# meteo_1.net
KiCad netlist of a schematic drawn in EAGLE
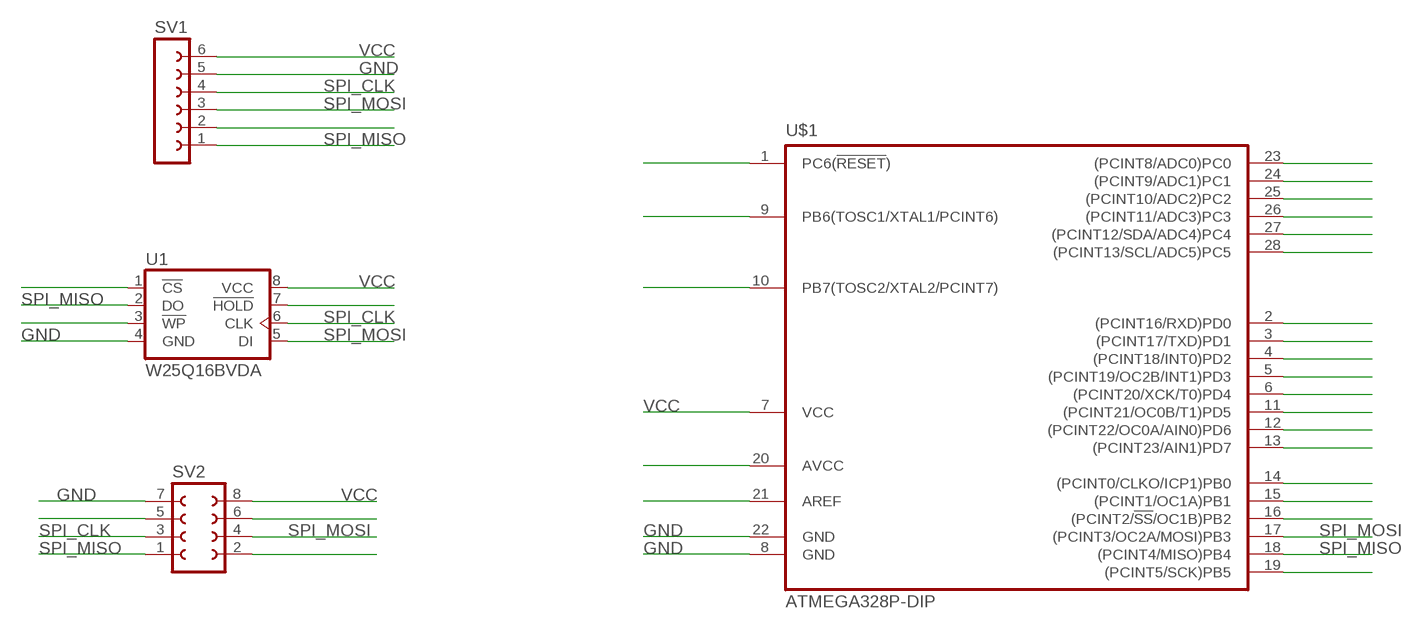
[diagram p0: schematic, sheet 1]

(export (version "E")
  (design (tool "Eeschema 10.0.6"))
  (components
    (comp (ref "SV1")
      (value "FE06-1")
      (footprint "eagle-import:FE06")
      (libsource (lib "eagle-import") (part "FE06-1"))
    )
    (comp (ref "SV2")
      (value "FE04-2")
      (footprint "eagle-import:FE04-2")
      (libsource (lib "eagle-import") (part "FE04-2"))
    )
    (comp (ref "U$1")
      (value "ATMEGA328P-DIP")
      (footprint "eagle-import:DIP762W53P254L3500H508Q28B")
      (libsource (lib "eagle-import") (part "ATMEGA328P-DIP"))
    )
    (comp (ref "U1")
      (value "W25Q16BVDA")
      (footprint "eagle-import:DIL08")
      (libsource (lib "eagle-import") (part "W25Q16BVDA"))
    )
  )
  (nets
    (net (code "1") (name "/GND") (class "Default")
      (node (ref "SV1") (pin "5") (pinfunction "5_5") (pintype "passive"))
      (node (ref "SV2") (pin "7") (pinfunction "7_7") (pintype "passive"))
      (node (ref "U$1") (pin "22") (pinfunction "GND_22") (pintype "power_in"))
      (node (ref "U$1") (pin "8") (pinfunction "GND_8") (pintype "power_in"))
      (node (ref "U1") (pin "4") (pinfunction "GND_4") (pintype "power_in"))
    )
    (net (code "2") (name "/SPI_CLK") (class "Default")
      (node (ref "SV1") (pin "4") (pinfunction "4_4") (pintype "passive"))
      (node (ref "SV2") (pin "3") (pinfunction "3_3") (pintype "passive"))
      (node (ref "U1") (pin "6") (pinfunction "CLK_6") (pintype "input"))
    )
    (net (code "3") (name "/SPI_MISO") (class "Default")
      (node (ref "SV1") (pin "1") (pinfunction "1_1") (pintype "passive"))
      (node (ref "SV2") (pin "1") (pinfunction "1_1") (pintype "passive"))
      (node (ref "U$1") (pin "18") (pinfunction "(PCINT4/MISO)PB4_18") (pintype "bidirectional"))
      (node (ref "U1") (pin "2") (pinfunction "DO_2") (pintype "output"))
    )
    (net (code "4") (name "/SPI_MOSI") (class "Default")
      (node (ref "SV1") (pin "3") (pinfunction "3_3") (pintype "passive"))
      (node (ref "SV2") (pin "4") (pinfunction "4_4") (pintype "passive"))
      (node (ref "U$1") (pin "17") (pinfunction "(PCINT3/OC2A/MOSI)PB3_17") (pintype "bidirectional"))
      (node (ref "U1") (pin "5") (pinfunction "DI_5") (pintype "input"))
    )
    (net (code "5") (name "/VCC") (class "Default")
      (node (ref "SV1") (pin "6") (pinfunction "6_6") (pintype "passive"))
      (node (ref "SV2") (pin "8") (pinfunction "8_8") (pintype "passive"))
      (node (ref "U$1") (pin "7") (pinfunction "VCC_7") (pintype "power_in"))
      (node (ref "U1") (pin "8") (pinfunction "VCC_8") (pintype "power_in"))
    )
    (net (code "6") (name "unconnected-(SV1-Pad2)") (class "Default")
      (node (ref "SV1") (pin "2") (pinfunction "2_2") (pintype "passive"))
    )
    (net (code "7") (name "unconnected-(SV2-Pad2)") (class "Default")
      (node (ref "SV2") (pin "2") (pinfunction "2_2") (pintype "passive"))
    )
    (net (code "8") (name "unconnected-(SV2-Pad5)") (class "Default")
      (node (ref "SV2") (pin "5") (pinfunction "5_5") (pintype "passive"))
    )
    (net (code "9") (name "unconnected-(SV2-Pad6)") (class "Default")
      (node (ref "SV2") (pin "6") (pinfunction "6_6") (pintype "passive"))
    )
    (net (code "10") (name "unconnected-(U$1-(PCINT0{slash}CLKO{slash}ICP1)PB0-Pad14)") (class "Default")
      (node (ref "U$1") (pin "14") (pinfunction "(PCINT0/CLKO/ICP1)PB0_14") (pintype "bidirectional"))
    )
    (net (code "11") (name "unconnected-(U$1-(PCINT1{slash}OC1A)PB1-Pad15)") (class "Default")
      (node (ref "U$1") (pin "15") (pinfunction "(PCINT1/OC1A)PB1_15") (pintype "bidirectional"))
    )
    (net (code "12") (name "unconnected-(U$1-(PCINT2{slash}~{SS}{slash}OC1B)PB2-Pad16)") (class "Default")
      (node (ref "U$1") (pin "16") (pinfunction "(PCINT2/~{SS}/OC1B)PB2_16") (pintype "bidirectional"))
    )
    (net (code "13") (name "unconnected-(U$1-(PCINT5{slash}SCK)PB5-Pad19)") (class "Default")
      (node (ref "U$1") (pin "19") (pinfunction "(PCINT5/SCK)PB5_19") (pintype "bidirectional"))
    )
    (net (code "14") (name "unconnected-(U$1-(PCINT8{slash}ADC0)PC0-Pad23)") (class "Default")
      (node (ref "U$1") (pin "23") (pinfunction "(PCINT8/ADC0)PC0_23") (pintype "bidirectional"))
    )
    (net (code "15") (name "unconnected-(U$1-(PCINT9{slash}ADC1)PC1-Pad24)") (class "Default")
      (node (ref "U$1") (pin "24") (pinfunction "(PCINT9/ADC1)PC1_24") (pintype "bidirectional"))
    )
    (net (code "16") (name "unconnected-(U$1-(PCINT10{slash}ADC2)PC2-Pad25)") (class "Default")
      (node (ref "U$1") (pin "25") (pinfunction "(PCINT10/ADC2)PC2_25") (pintype "bidirectional"))
    )
    (net (code "17") (name "unconnected-(U$1-(PCINT11{slash}ADC3)PC3-Pad26)") (class "Default")
      (node (ref "U$1") (pin "26") (pinfunction "(PCINT11/ADC3)PC3_26") (pintype "bidirectional"))
    )
    (net (code "18") (name "unconnected-(U$1-(PCINT12{slash}SDA{slash}ADC4)PC4-Pad27)") (class "Default")
      (node (ref "U$1") (pin "27") (pinfunction "(PCINT12/SDA/ADC4)PC4_27") (pintype "bidirectional"))
    )
    (net (code "19") (name "unconnected-(U$1-(PCINT13{slash}SCL{slash}ADC5)PC5-Pad28)") (class "Default")
      (node (ref "U$1") (pin "28") (pinfunction "(PCINT13/SCL/ADC5)PC5_28") (pintype "bidirectional"))
    )
    (net (code "20") (name "unconnected-(U$1-(PCINT16{slash}RXD)PD0-Pad2)") (class "Default")
      (node (ref "U$1") (pin "2") (pinfunction "(PCINT16/RXD)PD0_2") (pintype "bidirectional"))
    )
    (net (code "21") (name "unconnected-(U$1-(PCINT17{slash}TXD)PD1-Pad3)") (class "Default")
      (node (ref "U$1") (pin "3") (pinfunction "(PCINT17/TXD)PD1_3") (pintype "bidirectional"))
    )
    (net (code "22") (name "unconnected-(U$1-(PCINT18{slash}INT0)PD2-Pad4)") (class "Default")
      (node (ref "U$1") (pin "4") (pinfunction "(PCINT18/INT0)PD2_4") (pintype "bidirectional"))
    )
    (net (code "23") (name "unconnected-(U$1-(PCINT19{slash}OC2B{slash}INT1)PD3-Pad5)") (class "Default")
      (node (ref "U$1") (pin "5") (pinfunction "(PCINT19/OC2B/INT1)PD3_5") (pintype "bidirectional"))
    )
    (net (code "24") (name "unconnected-(U$1-(PCINT20{slash}XCK{slash}T0)PD4-Pad6)") (class "Default")
      (node (ref "U$1") (pin "6") (pinfunction "(PCINT20/XCK/T0)PD4_6") (pintype "bidirectional"))
    )
    (net (code "25") (name "unconnected-(U$1-(PCINT21{slash}OC0B{slash}T1)PD5-Pad11)") (class "Default")
      (node (ref "U$1") (pin "11") (pinfunction "(PCINT21/OC0B/T1)PD5_11") (pintype "bidirectional"))
    )
    (net (code "26") (name "unconnected-(U$1-(PCINT22{slash}OC0A{slash}AIN0)PD6-Pad12)") (class "Default")
      (node (ref "U$1") (pin "12") (pinfunction "(PCINT22/OC0A/AIN0)PD6_12") (pintype "bidirectional"))
    )
    (net (code "27") (name "unconnected-(U$1-(PCINT23{slash}AIN1)PD7-Pad13)") (class "Default")
      (node (ref "U$1") (pin "13") (pinfunction "(PCINT23/AIN1)PD7_13") (pintype "bidirectional"))
    )
    (net (code "28") (name "unconnected-(U$1-AREF-Pad21)") (class "Default")
      (node (ref "U$1") (pin "21") (pinfunction "AREF_21") (pintype "bidirectional"))
    )
    (net (code "29") (name "unconnected-(U$1-AVCC-Pad20)") (class "Default")
      (node (ref "U$1") (pin "20") (pinfunction "AVCC_20") (pintype "power_in"))
    )
    (net (code "30") (name "unconnected-(U$1-PB6(TOSC1{slash}XTAL1{slash}PCINT6)-Pad9)") (class "Default")
      (node (ref "U$1") (pin "9") (pinfunction "PB6(TOSC1/XTAL1/PCINT6)_9") (pintype "bidirectional"))
    )
    (net (code "31") (name "unconnected-(U$1-PB7(TOSC2{slash}XTAL2{slash}PCINT7)-Pad10)") (class "Default")
      (node (ref "U$1") (pin "10") (pinfunction "PB7(TOSC2/XTAL2/PCINT7)_10") (pintype "bidirectional"))
    )
    (net (code "32") (name "unconnected-(U$1-PC6(~{RESET})-Pad1)") (class "Default")
      (node (ref "U$1") (pin "1") (pinfunction "PC6(~{RESET})_1") (pintype "input"))
    )
    (net (code "33") (name "unconnected-(U1-~{CS}-Pad1)") (class "Default")
      (node (ref "U1") (pin "1") (pinfunction "~{CS}_1") (pintype "input"))
    )
    (net (code "34") (name "unconnected-(U1-~{HOLD}-Pad7)") (class "Default")
      (node (ref "U1") (pin "7") (pinfunction "~{HOLD}_7") (pintype "input"))
    )
    (net (code "35") (name "unconnected-(U1-~{WP}-Pad3)") (class "Default")
      (node (ref "U1") (pin "3") (pinfunction "~{WP}_3") (pintype "input"))
    )
  )
)
